# capstone_v1_1.net
KiCad netlist of a schematic drawn in Altium Designer
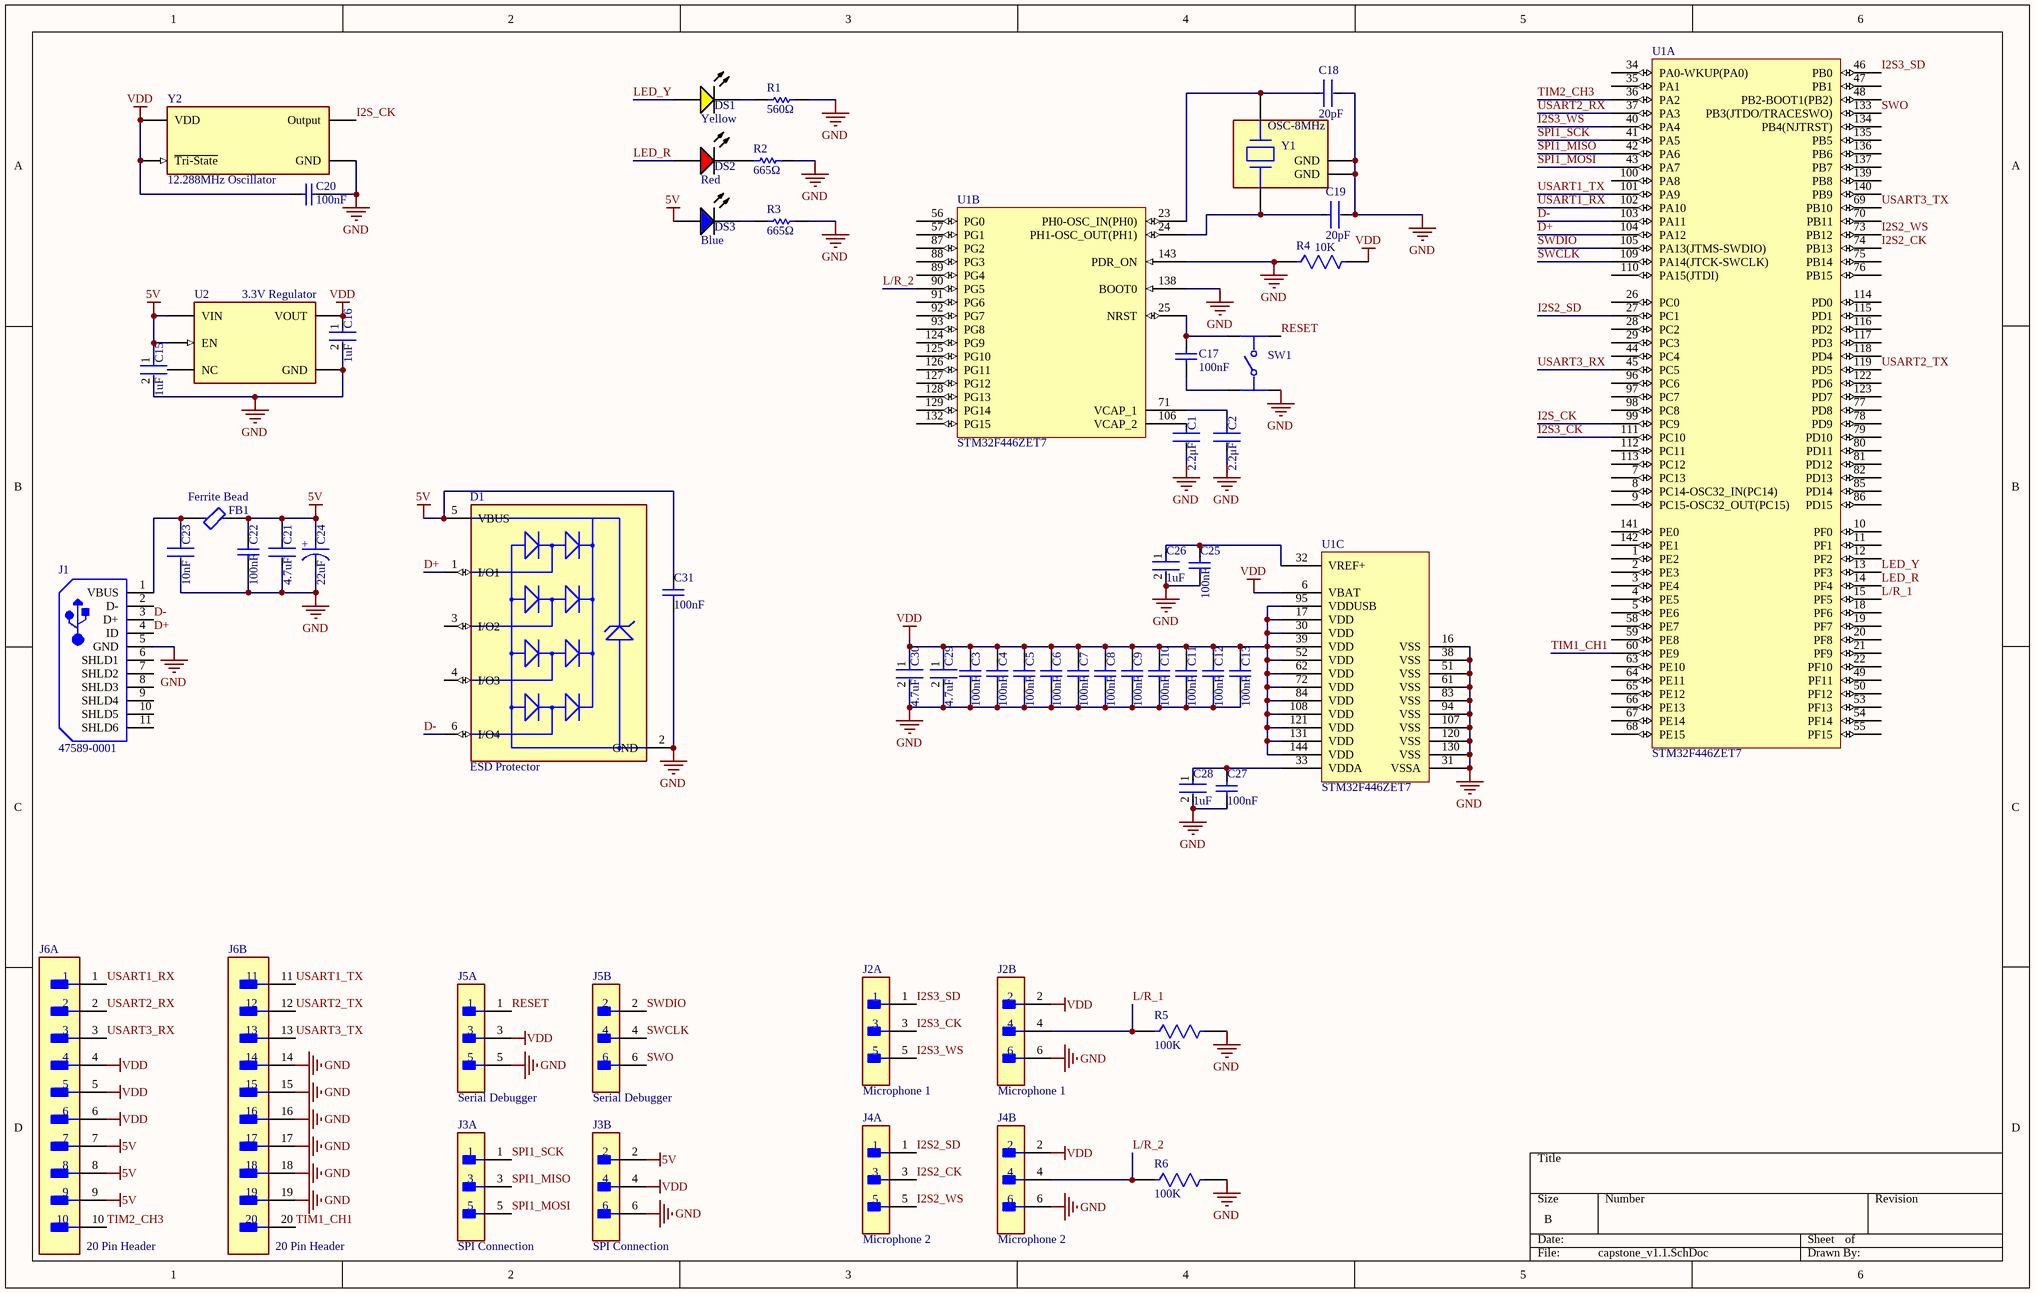
[diagram p0: capstone_v1.1.SchDoc]

(export (version "E")
  (design (tool "Eeschema 10.0.6"))
  (components
    (comp (ref "C1")
      (value "2.2μF")
      (footprint "FP-C1608-080-0_1-MFG")
      (description "Multilayer Ceramic Capacitors 2.2μF ±10% 35V X5R SMD 0603\r\nC1608X5R1V225K080AC")
      (fields (field (name "TOLERANCE") "10%") (field (name "VOLTAGE") "35V"))
      (libsource (lib "Altium Content Vault") (part "236180d848d6139a670b325ea6854c9"))
    )
    (comp (ref "C2")
      (value "2.2μF")
      (footprint "FP-C1608-080-0_1-MFG")
      (description "Multilayer Ceramic Capacitors 2.2μF ±10% 35V X5R SMD 0603\r\nC1608X5R1V225K080AC")
      (fields (field (name "TOLERANCE") "10%") (field (name "VOLTAGE") "35V"))
      (libsource (lib "Altium Content Vault") (part "236180d848d6139a670b325ea6854c9"))
    )
    (comp (ref "C3")
      (value "100nF")
      (footprint "SAMS-C0603-2_M")
      (fields (field (name "MANUFACTURER") "Samsung Electro-Mechanics"))
      (libsource (lib "Altium Content Vault") (part "CAP-NP-2"))
    )
    (comp (ref "C4")
      (value "100nF")
      (footprint "SAMS-C0603-2_M")
      (fields (field (name "MANUFACTURER") "Samsung Electro-Mechanics"))
      (libsource (lib "Altium Content Vault") (part "CAP-NP-2"))
    )
    (comp (ref "C5")
      (value "100nF")
      (footprint "SAMS-C0603-2_M")
      (fields (field (name "MANUFACTURER") "Samsung Electro-Mechanics"))
      (libsource (lib "Altium Content Vault") (part "CAP-NP-2"))
    )
    (comp (ref "C6")
      (value "100nF")
      (footprint "SAMS-C0603-2_M")
      (fields (field (name "MANUFACTURER") "Samsung Electro-Mechanics"))
      (libsource (lib "Altium Content Vault") (part "CAP-NP-2"))
    )
    (comp (ref "C7")
      (value "100nF")
      (footprint "SAMS-C0603-2_M")
      (fields (field (name "MANUFACTURER") "Samsung Electro-Mechanics"))
      (libsource (lib "Altium Content Vault") (part "CAP-NP-2"))
    )
    (comp (ref "C8")
      (value "100nF")
      (footprint "SAMS-C0603-2_M")
      (fields (field (name "MANUFACTURER") "Samsung Electro-Mechanics"))
      (libsource (lib "Altium Content Vault") (part "CAP-NP-2"))
    )
    (comp (ref "C9")
      (value "100nF")
      (footprint "SAMS-C0603-2_M")
      (fields (field (name "MANUFACTURER") "Samsung Electro-Mechanics"))
      (libsource (lib "Altium Content Vault") (part "CAP-NP-2"))
    )
    (comp (ref "C10")
      (value "100nF")
      (footprint "SAMS-C0603-2_M")
      (fields (field (name "MANUFACTURER") "Samsung Electro-Mechanics"))
      (libsource (lib "Altium Content Vault") (part "CAP-NP-2"))
    )
    (comp (ref "C11")
      (value "100nF")
      (footprint "SAMS-C0603-2_M")
      (fields (field (name "MANUFACTURER") "Samsung Electro-Mechanics"))
      (libsource (lib "Altium Content Vault") (part "CAP-NP-2"))
    )
    (comp (ref "C12")
      (value "100nF")
      (footprint "SAMS-C0603-2_M")
      (fields (field (name "MANUFACTURER") "Samsung Electro-Mechanics"))
      (libsource (lib "Altium Content Vault") (part "CAP-NP-2"))
    )
    (comp (ref "C13")
      (value "100nF")
      (footprint "SAMS-C0603-2_M")
      (fields (field (name "MANUFACTURER") "Samsung Electro-Mechanics"))
      (libsource (lib "Altium Content Vault") (part "CAP-NP-2"))
    )
    (comp (ref "C15")
      (value "1uF")
      (footprint "FP-0603-L_1_6_0_15-W_0_81-IPC_A")
      (description "General Purpose Ceramic Capacitor, 0603, 1uF, 10%, X5R, 15%, 10V\r\n0603ZD105KAT2A")
      (fields (field (name "TOLERANCE") "10%") (field (name "VOLTAGE") "10V"))
      (libsource (lib "Altium Content Vault") (part "02cd4be3c70576c341d710602a673aa"))
    )
    (comp (ref "C16")
      (value "1uF")
      (footprint "FP-0603-L_1_6_0_15-W_0_81-IPC_A")
      (description "General Purpose Ceramic Capacitor, 0603, 1uF, 10%, X5R, 15%, 10V\r\n0603ZD105KAT2A")
      (fields (field (name "TOLERANCE") "10%") (field (name "VOLTAGE") "10V"))
      (libsource (lib "Altium Content Vault") (part "02cd4be3c70576c341d710602a673aa"))
    )
    (comp (ref "C17")
      (value "100nF")
      (footprint "SAMS-C0603-2_M")
      (fields (field (name "MANUFACTURER") "Samsung Electro-Mechanics"))
      (libsource (lib "Altium Content Vault") (part "CAP-NP-2"))
    )
    (comp (ref "C18")
      (value "20pF")
      (footprint "FP-C0603C-CF-MFG")
      (description "CAP CER 20PF 50V 5% NP0 0603\r\nC0603C200J5GACTU")
      (fields
        (field (name "MANUFACTURER PART NUMBER") "C0603C200J5GACTU")
        (field (name "MANUFACTURER") "KEMET")
      )
      (libsource (lib "Altium Content Vault") (part "b4654b650e69147ec39a6b967a45e02"))
    )
    (comp (ref "C19")
      (value "20pF")
      (footprint "FP-C0603C-CF-MFG")
      (description "CAP CER 20PF 50V 5% NP0 0603\r\nC0603C200J5GACTU")
      (fields
        (field (name "MANUFACTURER PART NUMBER") "C0603C200J5GACTU")
        (field (name "MANUFACTURER") "KEMET")
      )
      (libsource (lib "Altium Content Vault") (part "b4654b650e69147ec39a6b967a45e02"))
    )
    (comp (ref "C20")
      (value "100nF")
      (footprint "SAMS-C0603-2_M")
      (fields (field (name "MANUFACTURER") "Samsung Electro-Mechanics"))
      (libsource (lib "Altium Content Vault") (part "CAP-NP-2"))
    )
    (comp (ref "C21")
      (value "4.7uF")
      (footprint "FP-C0603-CG-MFG")
      (description "CAP CER 4.7UF 6.3V X5R 0603\r\nC0603C475K9PACTU")
      (fields (field (name "TOLERANCE") "10%") (field (name "MANUFACTURER") "Kemet"))
      (libsource (lib "") (part "11868f565c42a9108669ba33697ecf6_1"))
    )
    (comp (ref "C22")
      (value "100nF")
      (footprint "SAMS-C0603-2_M")
      (fields (field (name "MANUFACTURER") "Samsung Electro-Mechanics"))
      (libsource (lib "Altium Content Vault") (part "CAP-NP-2"))
    )
    (comp (ref "C23")
      (value "10nF")
      (footprint "FP-0603-L_1_6_0_15-W_0_81-MFG")
      (description "General Purpose Ceramic Capacitor, 0603, 10nF, 10%, X7R, 15%, 50V")
      (fields (field (name "VOLTAGE") "50V") (field (name "TOLERANCE") "10%"))
      (libsource (lib "") (part "02cd4be3c70576c341d710602a673aa_1"))
    )
    (comp (ref "C24")
      (value "22uF")
      (footprint "FP-T491C226K010AT-MFG")
      (description "CAP TANT 22UF 10% 10V 2312\r\nT491C226K010AT")
      (fields (field (name "TOLERANCE") "20%") (field (name "VOLTAGE") "10V"))
      (libsource (lib "Altium Content Vault") (part "a00bbbee19879c290e62620ae7e47b1"))
    )
    (comp (ref "C25")
      (value "100nF")
      (footprint "SAMS-C0603-2_M")
      (fields (field (name "MANUFACTURER") "Samsung Electro-Mechanics"))
      (libsource (lib "Altium Content Vault") (part "CAP-NP-2"))
    )
    (comp (ref "C26")
      (value "1uF")
      (footprint "FP-0603-L_1_6_0_15-W_0_81-IPC_A")
      (description "General Purpose Ceramic Capacitor, 0603, 1uF, 10%, X5R, 15%, 10V\r\n0603ZD105KAT2A")
      (fields (field (name "TOLERANCE") "10%") (field (name "VOLTAGE") "10V"))
      (libsource (lib "Altium Content Vault") (part "02cd4be3c70576c341d710602a673aa"))
    )
    (comp (ref "C27")
      (value "100nF")
      (footprint "SAMS-C0603-2_M")
      (fields (field (name "MANUFACTURER") "Samsung Electro-Mechanics"))
      (libsource (lib "Altium Content Vault") (part "CAP-NP-2"))
    )
    (comp (ref "C28")
      (value "1uF")
      (footprint "FP-0603-L_1_6_0_15-W_0_81-IPC_A")
      (description "General Purpose Ceramic Capacitor, 0603, 1uF, 10%, X5R, 15%, 10V\r\n0603ZD105KAT2A")
      (fields (field (name "TOLERANCE") "10%") (field (name "VOLTAGE") "10V"))
      (libsource (lib "Altium Content Vault") (part "02cd4be3c70576c341d710602a673aa"))
    )
    (comp (ref "C29")
      (value "4.7uF")
      (footprint "FP-C0603-CG-MFG")
      (description "CAP CER 4.7UF 6.3V X5R 0603\r\nC0603C475K9PACTU")
      (fields (field (name "TOLERANCE") "10%") (field (name "MANUFACTURER") "Kemet"))
      (libsource (lib "Altium Content Vault") (part "11868f565c42a9108669ba33697ecf6"))
    )
    (comp (ref "C30")
      (value "4.7uF")
      (footprint "FP-C0603-CG-MFG")
      (description "CAP CER 4.7UF 6.3V X5R 0603\r\nC0603C475K9PACTU")
      (fields (field (name "TOLERANCE") "10%") (field (name "MANUFACTURER") "Kemet"))
      (libsource (lib "Altium Content Vault") (part "11868f565c42a9108669ba33697ecf6"))
    )
    (comp (ref "C31")
      (value "100nF")
      (footprint "SAMS-C0603-2_M")
      (fields (field (name "MANUFACTURER") "Samsung Electro-Mechanics"))
      (libsource (lib "Altium Content Vault") (part "CAP-NP-2"))
    )
    (comp (ref "D1")
      (value "ESD Protector")
      (footprint "FP-SOT23-6L-MFG")
      (description "TVS DIODE 5.25V 17V SOT23-6\r\nUSBLC6-4SC6")
      (fields
        (field (name "MANUFACTURER") "STMicroelectronics")
        (field (name "OCTOPART") "https://octopart.com/usblc6-4sc6-stmicroelectronics-347147")
      )
      (libsource (lib "Altium Content Vault") (part "3e70b616ccdc4c88b528e1820c4a7da"))
    )
    (comp (ref "DS1")
      (value "Yellow")
      (footprint "VISH-TLMY1000_V")
      (description "Low Current LED, 40 mW, -40 to 100 degC, 2-Pin SMD, RoHS, Tape and Reel\r\nTLMY1000-GS08")
      (fields (field (name "MANUFACTURER") "Vishay"))
      (libsource (lib "Altium Content Vault") (part "LED-YELLOW-AK-2"))
    )
    (comp (ref "DS2")
      (value "Red")
      (footprint "AVAG-HSMX-C190_V")
      (description "LED Uni-Color Red, 65 mW, 20 mA, -40 to 85 degC, 2-Pin SMD, RoHS, Tape and Reel\r\nHSMH-C190")
      (libsource (lib "Altium Content Vault") (part "LED-RED-AK-2"))
    )
    (comp (ref "DS3")
      (value "Blue")
      (footprint "AVAG-HSMX-C190_V")
      (description "LED Uni-Color Blue, 78 mW, 20 mA, -40 to 85 degC, 2-Pin SMD, RoHS, Tape and Reel\r\nHSMR-C190")
      (libsource (lib "Altium Content Vault") (part "LED-BLUE-AK-2"))
    )
    (comp (ref "FB1")
      (value "Ferrite Bead")
      (footprint "FP-BLM15-0_05-IPC_A")
      (description "Chip Ferrite Bead, 0402, 220Ω @ 100MHz, 0.1Ω, 25%, 1.4A\r\nBLM15PX221SN1D")
      (fields (field (name "TOLERANCE") "25%"))
      (libsource (lib "Altium Content Vault") (part "5f30dd21d616792df468990f7003faa"))
    )
    (comp (ref "J1")
      (value "47589-0001")
      (footprint "MOLX-47589-0001_V")
      (description "Right Angle Female Type AB Micro USB Connector, 30 V, 1.8 A, -30 to 85 degC, RoHS, Tape and Reel")
      (fields (field (name "MANUFACTURER") "Molex"))
      (libsource (lib "Altium Content Vault") (part "USB-5-6SHLD"))
    )
    (comp (ref "J2")
      (value "Microphone 1")
      (footprint "FP-M20-9980346-MFG")
      (description "CONN HEADER VERT 6POS 2.54MM\r\nM20-9980346")
      (fields (field (name "MANUFACTURER PART NUMBER") "M20-9980346") (field (name "MANUFACTURER") "Harwin"))
      (libsource (lib "Altium Content Vault") (part "2654a11fb13586ecb194516b1c997bc"))
    )
    (comp (ref "J3")
      (value "SPI Connection")
      (footprint "FP-M20-9980346-MFG")
      (description "CONN HEADER VERT 6POS 2.54MM\r\nM20-9980346")
      (fields (field (name "MANUFACTURER PART NUMBER") "M20-9980346") (field (name "MANUFACTURER") "Harwin"))
      (libsource (lib "Altium Content Vault") (part "2654a11fb13586ecb194516b1c997bc"))
    )
    (comp (ref "J4")
      (value "Microphone 2")
      (footprint "FP-M20-9980346-MFG")
      (description "CONN HEADER VERT 6POS 2.54MM\r\nM20-9980346")
      (fields (field (name "MANUFACTURER PART NUMBER") "M20-9980346") (field (name "MANUFACTURER") "Harwin"))
      (libsource (lib "Altium Content Vault") (part "2654a11fb13586ecb194516b1c997bc"))
    )
    (comp (ref "J5")
      (value "Serial Debugger")
      (footprint "FP-M20-9980346-MFG")
      (description "CONN HEADER VERT 6POS 2.54MM\r\nM20-9980346")
      (fields (field (name "MANUFACTURER PART NUMBER") "M20-9980346") (field (name "MANUFACTURER") "Harwin"))
      (libsource (lib "Altium Content Vault") (part "2654a11fb13586ecb194516b1c997bc"))
    )
    (comp (ref "J6")
      (value "20 Pin Header")
      (footprint "FP-TSW-110-08-G-D-MFG")
      (description "CONN HEADER VERT 20POS 2.54MM\r\nTSW-110-08-G-D")
      (fields
        (field (name "MANUFACTURER") "Samtec")
        (field (name "MANUFACTURER PART NUMBER") "TSW-110-08-G-D")
      )
      (libsource (lib "Altium Content Vault") (part "77e5b6e48cf913a9c6d5f7856d88bd2"))
    )
    (comp (ref "R1")
      (value "560Ω")
      (footprint "RESC1608X55X30ML15T15")
      (libsource (lib "Altium Content Vault") (part "RES-2"))
    )
    (comp (ref "R2")
      (value "665Ω")
      (footprint "RESC1608X55X30ML15T15")
      (description "ERJ-3EKF6650V")
      (fields (field (name "MANUFACTURER") "Panasonic"))
      (libsource (lib "Altium Content Vault") (part "RES"))
    )
    (comp (ref "R3")
      (value "665Ω")
      (footprint "RESC1608X55X30ML15T15")
      (description "ERJ-3EKF6650V")
      (fields (field (name "MANUFACTURER") "Panasonic"))
      (libsource (lib "Altium Content Vault") (part "RES"))
    )
    (comp (ref "R4")
      (value "10K")
      (footprint "FP-MCT0603-IPC_C")
      (description "RES SMD 100 OHM 1% 1/8W 0603\r\nMCT06030C1002FP500")
      (fields (field (name "TOLERANCE") "1%"))
      (libsource (lib "Altium Content Vault") (part "1029c3af85768c4190bb7ad29bc67b5"))
    )
    (comp (ref "R5")
      (value "100K")
      (footprint "FP-RC0603-0_55-MFG")
      (description "RES SMD 100K OHM 1% 1/10W 0603\r\nRC0603FR-07100KL")
      (fields (field (name "TOLERANCE") "1%"))
      (libsource (lib "Altium Content Vault") (part "1029c3af85768c4190bb7ad29bc67b5"))
    )
    (comp (ref "R6")
      (value "100K")
      (footprint "FP-RC0603-0_55-MFG")
      (description "RES SMD 100K OHM 1% 1/10W 0603\r\nRC0603FR-07100KL")
      (fields (field (name "TOLERANCE") "1%"))
      (libsource (lib "Altium Content Vault") (part "1029c3af85768c4190bb7ad29bc67b5"))
    )
    (comp (ref "SW1")
      (value "PTS645SM43SMTR92LFS")
      (footprint "FP-PTS645SM43SMTR92LFS-MFG")
      (description "SWITCH TACTILE SPST-NO 0.05A 12V")
      (libsource (lib "Altium Content Vault") (part "1adf0dd01260c80cf25a44bfd6b99ba"))
    )
    (comp (ref "U1")
      (value "STM32F446ZET7")
      (footprint "STM-LQFP144_M")
      (libsource (lib "Altium Content Vault") (part "MC-ARM-STM32F446-LQFP144"))
    )
    (comp (ref "U2")
      (value "3.3V Regulator")
      (footprint "FP-UJ-5-IPC_B")
      (description "IC REG LINEAR 3.3V 150MA TSOT5\r\nADP121-AUJZ33R7")
      (libsource (lib "Altium Content Vault") (part "0a093dae7315cdc977fd108dde87457"))
    )
    (comp (ref "Y1")
      (value "OSC-8MHz")
      (footprint "FP-ABM3B-MFG")
      (description "Crystal 8MHz ±20ppm 18pF SMD-4 5mm x 3.2mm\r\nABM3B-8.000MHZ-B2-T")
      (fields (field (name "TOLERANCE") "20ppm"))
      (libsource (lib "Altium Content Vault") (part "48e526d86b7f2615d98721063c72f49"))
    )
    (comp (ref "Y2")
      (value "12.288MHz Oscillator")
      (footprint "FP-ASFL1-MFG")
      (description "XTAL Oscillator 12.288MHz ±50ppm HCMOS, TTL 3.3V 4-SMD 5mm x 3.2mm\r\nASFL1-12.288MHZ-EC-T")
      (libsource (lib "Altium Content Vault") (part "47df00dc2349451232cb22fac08fbff"))
    )
  )
  (nets
    (net (code "1") (name "/D+") (class "Default")
      (node (ref "D1") (pin "1") (pinfunction "I/O1_1") (pintype "bidirectional"))
      (node (ref "J1") (pin "4") (pinfunction "ID_4") (pintype "passive"))
      (node (ref "U1") (pin "104") (pinfunction "PA12_104") (pintype "bidirectional"))
    )
    (net (code "2") (name "/D-") (class "Default")
      (node (ref "D1") (pin "6") (pinfunction "I/O4_6") (pintype "bidirectional"))
      (node (ref "J1") (pin "3") (pinfunction "D+_3") (pintype "passive"))
      (node (ref "U1") (pin "103") (pinfunction "PA11_103") (pintype "bidirectional"))
    )
    (net (code "3") (name "/I2S2_CK") (class "Default")
      (node (ref "J4") (pin "3") (pinfunction "3_3") (pintype "passive"))
      (node (ref "U1") (pin "74") (pinfunction "PB13_74") (pintype "bidirectional"))
    )
    (net (code "4") (name "/I2S2_SD") (class "Default")
      (node (ref "J4") (pin "1") (pinfunction "1_1") (pintype "passive"))
      (node (ref "U1") (pin "27") (pinfunction "PC1_27") (pintype "bidirectional"))
    )
    (net (code "5") (name "/I2S2_WS") (class "Default")
      (node (ref "J4") (pin "5") (pinfunction "5_5") (pintype "passive"))
      (node (ref "U1") (pin "73") (pinfunction "PB12_73") (pintype "bidirectional"))
    )
    (net (code "6") (name "/I2S3_CK") (class "Default")
      (node (ref "J2") (pin "3") (pinfunction "3_3") (pintype "passive"))
      (node (ref "U1") (pin "111") (pinfunction "PC10_111") (pintype "bidirectional"))
    )
    (net (code "7") (name "/I2S3_SD") (class "Default")
      (node (ref "J2") (pin "1") (pinfunction "1_1") (pintype "passive"))
      (node (ref "U1") (pin "46") (pinfunction "PB0_46") (pintype "bidirectional"))
    )
    (net (code "8") (name "/I2S3_WS") (class "Default")
      (node (ref "J2") (pin "5") (pinfunction "5_5") (pintype "passive"))
      (node (ref "U1") (pin "40") (pinfunction "PA4_40") (pintype "bidirectional"))
    )
    (net (code "9") (name "/I2S_CK") (class "Default")
      (node (ref "U1") (pin "99") (pinfunction "PC9_99") (pintype "bidirectional"))
      (node (ref "Y2") (pin "3") (pinfunction "Output_3") (pintype "passive"))
    )
    (net (code "10") (name "/LED_R") (class "Default")
      (node (ref "DS2") (pin "1") (pinfunction "A_1") (pintype "passive"))
      (node (ref "U1") (pin "14") (pinfunction "PF4_14") (pintype "bidirectional"))
    )
    (net (code "11") (name "/LED_Y") (class "Default")
      (node (ref "DS1") (pin "1") (pinfunction "A_1") (pintype "passive"))
      (node (ref "U1") (pin "13") (pinfunction "PF3_13") (pintype "bidirectional"))
    )
    (net (code "12") (name "/L{slash}R_1") (class "Default")
      (node (ref "J2") (pin "4") (pinfunction "4_4") (pintype "passive"))
      (node (ref "R5") (pin "1") (pinfunction "1_1") (pintype "passive"))
      (node (ref "U1") (pin "15") (pinfunction "PF5_15") (pintype "bidirectional"))
    )
    (net (code "13") (name "/L{slash}R_2") (class "Default")
      (node (ref "J4") (pin "4") (pinfunction "4_4") (pintype "passive"))
      (node (ref "R6") (pin "1") (pinfunction "1_1") (pintype "passive"))
      (node (ref "U1") (pin "90") (pinfunction "PG5_90") (pintype "bidirectional"))
    )
    (net (code "14") (name "/RESET") (class "Default")
      (node (ref "J5") (pin "1") (pinfunction "1_1") (pintype "passive"))
      (node (ref "SW1") (pin "2") (pinfunction "2_2") (pintype "passive"))
    )
    (net (code "15") (name "/SPI1_MISO") (class "Default")
      (node (ref "J3") (pin "3") (pinfunction "3_3") (pintype "passive"))
      (node (ref "U1") (pin "42") (pinfunction "PA6_42") (pintype "bidirectional"))
    )
    (net (code "16") (name "/SPI1_MOSI") (class "Default")
      (node (ref "J3") (pin "5") (pinfunction "5_5") (pintype "passive"))
      (node (ref "U1") (pin "43") (pinfunction "PA7_43") (pintype "bidirectional"))
    )
    (net (code "17") (name "/SPI1_SCK") (class "Default")
      (node (ref "J3") (pin "1") (pinfunction "1_1") (pintype "passive"))
      (node (ref "U1") (pin "41") (pinfunction "PA5_41") (pintype "bidirectional"))
    )
    (net (code "18") (name "/SWCLK") (class "Default")
      (node (ref "J5") (pin "4") (pinfunction "4_4") (pintype "passive"))
      (node (ref "U1") (pin "109") (pinfunction "PA14(JTCK-SWCLK)_109") (pintype "bidirectional"))
    )
    (net (code "19") (name "/SWDIO") (class "Default")
      (node (ref "J5") (pin "2") (pinfunction "2_2") (pintype "passive"))
      (node (ref "U1") (pin "105") (pinfunction "PA13(JTMS-SWDIO)_105") (pintype "bidirectional"))
    )
    (net (code "20") (name "/SWO") (class "Default")
      (node (ref "J5") (pin "6") (pinfunction "6_6") (pintype "passive"))
      (node (ref "U1") (pin "133") (pinfunction "PB3(JTDO/TRACESWO)_133") (pintype "bidirectional"))
    )
    (net (code "21") (name "/TIM1_CH1") (class "Default")
      (node (ref "J6") (pin "20") (pinfunction "20_20") (pintype "passive"))
      (node (ref "U1") (pin "60") (pinfunction "PE9_60") (pintype "bidirectional"))
    )
    (net (code "22") (name "/TIM2_CH3") (class "Default")
      (node (ref "J6") (pin "10") (pinfunction "10_10") (pintype "passive"))
      (node (ref "U1") (pin "36") (pinfunction "PA2_36") (pintype "bidirectional"))
    )
    (net (code "23") (name "/USART1_RX") (class "Default")
      (node (ref "J6") (pin "1") (pinfunction "1_1") (pintype "passive"))
      (node (ref "U1") (pin "102") (pinfunction "PA10_102") (pintype "bidirectional"))
    )
    (net (code "24") (name "/USART1_TX") (class "Default")
      (node (ref "J6") (pin "11") (pinfunction "11_11") (pintype "passive"))
      (node (ref "U1") (pin "101") (pinfunction "PA9_101") (pintype "bidirectional"))
    )
    (net (code "25") (name "/USART2_RX") (class "Default")
      (node (ref "J6") (pin "2") (pinfunction "2_2") (pintype "passive"))
      (node (ref "U1") (pin "37") (pinfunction "PA3_37") (pintype "bidirectional"))
    )
    (net (code "26") (name "/USART2_TX") (class "Default")
      (node (ref "J6") (pin "12") (pinfunction "12_12") (pintype "passive"))
      (node (ref "U1") (pin "119") (pinfunction "PD5_119") (pintype "bidirectional"))
    )
    (net (code "27") (name "/USART3_RX") (class "Default")
      (node (ref "J6") (pin "3") (pinfunction "3_3") (pintype "passive"))
      (node (ref "U1") (pin "45") (pinfunction "PC5_45") (pintype "bidirectional"))
    )
    (net (code "28") (name "/USART3_TX") (class "Default")
      (node (ref "J6") (pin "13") (pinfunction "13_13") (pintype "passive"))
      (node (ref "U1") (pin "69") (pinfunction "PB10_69") (pintype "bidirectional"))
    )
    (net (code "29") (name "5V") (class "Default")
      (node (ref "C15") (pin "1") (pinfunction "1_1") (pintype "passive"))
      (node (ref "C21") (pin "1") (pinfunction "1_1") (pintype "passive"))
      (node (ref "C22") (pin "2") (pinfunction "2_2") (pintype "passive"))
      (node (ref "C24") (pin "2") (pinfunction "A_2") (pintype "passive"))
      (node (ref "C31") (pin "2") (pinfunction "2_2") (pintype "passive"))
      (node (ref "D1") (pin "5") (pinfunction "VBUS_5") (pintype "power_in"))
      (node (ref "DS3") (pin "1") (pinfunction "A_1") (pintype "passive"))
      (node (ref "FB1") (pin "2") (pinfunction "2_2") (pintype "passive"))
      (node (ref "J3") (pin "2") (pinfunction "2_2") (pintype "passive"))
      (node (ref "J6") (pin "7") (pinfunction "7_7") (pintype "passive"))
      (node (ref "J6") (pin "8") (pinfunction "8_8") (pintype "passive"))
      (node (ref "J6") (pin "9") (pinfunction "9_9") (pintype "passive"))
      (node (ref "U2") (pin "1") (pinfunction "VIN_1") (pintype "power_in"))
      (node (ref "U2") (pin "3") (pinfunction "EN_3") (pintype "input"))
    )
    (net (code "30") (name "GND") (class "Default")
      (node (ref "C1") (pin "1") (pinfunction "1_1") (pintype "passive"))
      (node (ref "C10") (pin "1") (pinfunction "1_1") (pintype "passive"))
      (node (ref "C11") (pin "1") (pinfunction "1_1") (pintype "passive"))
      (node (ref "C12") (pin "1") (pinfunction "1_1") (pintype "passive"))
      (node (ref "C13") (pin "1") (pinfunction "1_1") (pintype "passive"))
      (node (ref "C15") (pin "2") (pinfunction "2_2") (pintype "passive"))
      (node (ref "C16") (pin "2") (pinfunction "2_2") (pintype "passive"))
      (node (ref "C18") (pin "2") (pinfunction "2_2") (pintype "passive"))
      (node (ref "C19") (pin "2") (pinfunction "2_2") (pintype "passive"))
      (node (ref "C2") (pin "1") (pinfunction "1_1") (pintype "passive"))
      (node (ref "C20") (pin "1") (pinfunction "1_1") (pintype "passive"))
      (node (ref "C21") (pin "2") (pinfunction "2_2") (pintype "passive"))
      (node (ref "C22") (pin "1") (pinfunction "1_1") (pintype "passive"))
      (node (ref "C23") (pin "2") (pinfunction "2_2") (pintype "passive"))
      (node (ref "C24") (pin "1") (pinfunction "C_1") (pintype "passive"))
      (node (ref "C25") (pin "1") (pinfunction "1_1") (pintype "passive"))
      (node (ref "C26") (pin "2") (pinfunction "2_2") (pintype "passive"))
      (node (ref "C27") (pin "1") (pinfunction "1_1") (pintype "passive"))
      (node (ref "C28") (pin "2") (pinfunction "2_2") (pintype "passive"))
      (node (ref "C29") (pin "2") (pinfunction "2_2") (pintype "passive"))
      (node (ref "C3") (pin "1") (pinfunction "1_1") (pintype "passive"))
      (node (ref "C30") (pin "2") (pinfunction "2_2") (pintype "passive"))
      (node (ref "C31") (pin "1") (pinfunction "1_1") (pintype "passive"))
      (node (ref "C4") (pin "1") (pinfunction "1_1") (pintype "passive"))
      (node (ref "C5") (pin "1") (pinfunction "1_1") (pintype "passive"))
      (node (ref "C6") (pin "1") (pinfunction "1_1") (pintype "passive"))
      (node (ref "C7") (pin "1") (pinfunction "1_1") (pintype "passive"))
      (node (ref "C8") (pin "1") (pinfunction "1_1") (pintype "passive"))
      (node (ref "C9") (pin "1") (pinfunction "1_1") (pintype "passive"))
      (node (ref "D1") (pin "2") (pinfunction "GND_2") (pintype "power_in"))
      (node (ref "J1") (pin "5") (pinfunction "GND_5") (pintype "passive"))
      (node (ref "J2") (pin "6") (pinfunction "6_6") (pintype "passive"))
      (node (ref "J3") (pin "6") (pinfunction "6_6") (pintype "passive"))
      (node (ref "J4") (pin "6") (pinfunction "6_6") (pintype "passive"))
      (node (ref "J5") (pin "5") (pinfunction "5_5") (pintype "passive"))
      (node (ref "J6") (pin "14") (pinfunction "14_14") (pintype "passive"))
      (node (ref "J6") (pin "15") (pinfunction "15_15") (pintype "passive"))
      (node (ref "J6") (pin "16") (pinfunction "16_16") (pintype "passive"))
      (node (ref "J6") (pin "17") (pinfunction "17_17") (pintype "passive"))
      (node (ref "J6") (pin "18") (pinfunction "18_18") (pintype "passive"))
      (node (ref "J6") (pin "19") (pinfunction "19_19") (pintype "passive"))
      (node (ref "R1") (pin "2") (pinfunction "2_2") (pintype "passive"))
      (node (ref "R2") (pin "2") (pinfunction "2_2") (pintype "passive"))
      (node (ref "R3") (pin "2") (pinfunction "2_2") (pintype "passive"))
      (node (ref "R4") (pin "1") (pinfunction "1_1") (pintype "passive"))
      (node (ref "R5") (pin "2") (pinfunction "2_2") (pintype "passive"))
      (node (ref "R6") (pin "2") (pinfunction "2_2") (pintype "passive"))
      (node (ref "SW1") (pin "4") (pinfunction "4_4") (pintype "passive"))
      (node (ref "U1") (pin "107") (pinfunction "VSS_107") (pintype "power_in"))
      (node (ref "U1") (pin "120") (pinfunction "VSS_120") (pintype "power_in"))
      (node (ref "U1") (pin "130") (pinfunction "VSS_130") (pintype "power_in"))
      (node (ref "U1") (pin "138") (pinfunction "BOOT0_138") (pintype "input"))
      (node (ref "U1") (pin "143") (pinfunction "PDR_ON_143") (pintype "input"))
      (node (ref "U1") (pin "16") (pinfunction "VSS_16") (pintype "power_in"))
      (node (ref "U1") (pin "31") (pinfunction "VSSA_31") (pintype "power_in"))
      (node (ref "U1") (pin "38") (pinfunction "VSS_38") (pintype "power_in"))
      (node (ref "U1") (pin "51") (pinfunction "VSS_51") (pintype "power_in"))
      (node (ref "U1") (pin "61") (pinfunction "VSS_61") (pintype "power_in"))
      (node (ref "U1") (pin "83") (pinfunction "VSS_83") (pintype "power_in"))
      (node (ref "U1") (pin "94") (pinfunction "VSS_94") (pintype "power_in"))
      (node (ref "U2") (pin "2") (pinfunction "GND_2") (pintype "power_in"))
      (node (ref "Y1") (pin "2") (pinfunction "GND_2") (pintype "power_in"))
      (node (ref "Y1") (pin "4") (pinfunction "GND_4") (pintype "power_in"))
      (node (ref "Y2") (pin "2") (pinfunction "GND_2") (pintype "power_in"))
    )
    (net (code "31") (name "Net-(C17-Pad1)") (class "Default")
      (node (ref "C17") (pin "1") (pinfunction "1_1") (pintype "passive"))
      (node (ref "SW1") (pin "3") (pinfunction "3_3") (pintype "passive"))
    )
    (net (code "32") (name "Net-(DS1-K)") (class "Default")
      (node (ref "DS1") (pin "2") (pinfunction "K_2") (pintype "passive"))
      (node (ref "R1") (pin "1") (pinfunction "1_1") (pintype "passive"))
    )
    (net (code "33") (name "Net-(DS2-K)") (class "Default")
      (node (ref "DS2") (pin "2") (pinfunction "K_2") (pintype "passive"))
      (node (ref "R2") (pin "1") (pinfunction "1_1") (pintype "passive"))
    )
    (net (code "34") (name "Net-(DS3-K)") (class "Default")
      (node (ref "DS3") (pin "2") (pinfunction "K_2") (pintype "passive"))
      (node (ref "R3") (pin "1") (pinfunction "1_1") (pintype "passive"))
    )
    (net (code "35") (name "Net-(J1-VBUS)") (class "Default")
      (node (ref "C23") (pin "1") (pinfunction "1_1") (pintype "passive"))
      (node (ref "FB1") (pin "1") (pinfunction "1_1") (pintype "passive"))
      (node (ref "J1") (pin "1") (pinfunction "VBUS_1") (pintype "passive"))
    )
    (net (code "36") (name "Net-(U1B-NRST)") (class "Default")
      (node (ref "C17") (pin "2") (pinfunction "2_2") (pintype "passive"))
      (node (ref "SW1") (pin "1") (pinfunction "1_1") (pintype "passive"))
      (node (ref "U1") (pin "25") (pinfunction "NRST_25") (pintype "bidirectional"))
    )
    (net (code "37") (name "Net-(U1B-PH0-OSC_IN(PH0))") (class "Default")
      (node (ref "C18") (pin "1") (pinfunction "1_1") (pintype "passive"))
      (node (ref "U1") (pin "23") (pinfunction "PH0-OSC_IN(PH0)_23") (pintype "bidirectional"))
      (node (ref "Y1") (pin "1") (pinfunction "1_1") (pintype "passive"))
    )
    (net (code "38") (name "Net-(U1B-PH1-OSC_OUT(PH1))") (class "Default")
      (node (ref "C19") (pin "1") (pinfunction "1_1") (pintype "passive"))
      (node (ref "U1") (pin "24") (pinfunction "PH1-OSC_OUT(PH1)_24") (pintype "bidirectional"))
      (node (ref "Y1") (pin "3") (pinfunction "3_3") (pintype "passive"))
    )
    (net (code "39") (name "Net-(U1B-VCAP_1)") (class "Default")
      (node (ref "C2") (pin "2") (pinfunction "2_2") (pintype "passive"))
      (node (ref "U1") (pin "71") (pinfunction "VCAP_1_71") (pintype "passive"))
    )
    (net (code "40") (name "Net-(U1B-VCAP_2)") (class "Default")
      (node (ref "C1") (pin "2") (pinfunction "2_2") (pintype "passive"))
      (node (ref "U1") (pin "106") (pinfunction "VCAP_2_106") (pintype "passive"))
    )
    (net (code "41") (name "Net-(U1C-VDDA)") (class "Default")
      (node (ref "C27") (pin "2") (pinfunction "2_2") (pintype "passive"))
      (node (ref "C28") (pin "1") (pinfunction "1_1") (pintype "passive"))
      (node (ref "U1") (pin "33") (pinfunction "VDDA_33") (pintype "power_in"))
    )
    (net (code "42") (name "Net-(U1C-VREF+)") (class "Default")
      (node (ref "C25") (pin "2") (pinfunction "2_2") (pintype "passive"))
      (node (ref "C26") (pin "1") (pinfunction "1_1") (pintype "passive"))
      (node (ref "U1") (pin "32") (pinfunction "VREF+_32") (pintype "power_in"))
    )
    (net (code "43") (name "VDD") (class "Default")
      (node (ref "C10") (pin "2") (pinfunction "2_2") (pintype "passive"))
      (node (ref "C11") (pin "2") (pinfunction "2_2") (pintype "passive"))
      (node (ref "C12") (pin "2") (pinfunction "2_2") (pintype "passive"))
      (node (ref "C13") (pin "2") (pinfunction "2_2") (pintype "passive"))
      (node (ref "C16") (pin "1") (pinfunction "1_1") (pintype "passive"))
      (node (ref "C20") (pin "2") (pinfunction "2_2") (pintype "passive"))
      (node (ref "C29") (pin "1") (pinfunction "1_1") (pintype "passive"))
      (node (ref "C3") (pin "2") (pinfunction "2_2") (pintype "passive"))
      (node (ref "C30") (pin "1") (pinfunction "1_1") (pintype "passive"))
      (node (ref "C4") (pin "2") (pinfunction "2_2") (pintype "passive"))
      (node (ref "C5") (pin "2") (pinfunction "2_2") (pintype "passive"))
      (node (ref "C6") (pin "2") (pinfunction "2_2") (pintype "passive"))
      (node (ref "C7") (pin "2") (pinfunction "2_2") (pintype "passive"))
      (node (ref "C8") (pin "2") (pinfunction "2_2") (pintype "passive"))
      (node (ref "C9") (pin "2") (pinfunction "2_2") (pintype "passive"))
      (node (ref "J2") (pin "2") (pinfunction "2_2") (pintype "passive"))
      (node (ref "J3") (pin "4") (pinfunction "4_4") (pintype "passive"))
      (node (ref "J4") (pin "2") (pinfunction "2_2") (pintype "passive"))
      (node (ref "J5") (pin "3") (pinfunction "3_3") (pintype "passive"))
      (node (ref "J6") (pin "4") (pinfunction "4_4") (pintype "passive"))
      (node (ref "J6") (pin "5") (pinfunction "5_5") (pintype "passive"))
      (node (ref "J6") (pin "6") (pinfunction "6_6") (pintype "passive"))
      (node (ref "R4") (pin "2") (pinfunction "2_2") (pintype "passive"))
      (node (ref "U1") (pin "108") (pinfunction "VDD_108") (pintype "power_in"))
      (node (ref "U1") (pin "121") (pinfunction "VDD_121") (pintype "power_in"))
      (node (ref "U1") (pin "131") (pinfunction "VDD_131") (pintype "power_in"))
      (node (ref "U1") (pin "144") (pinfunction "VDD_144") (pintype "power_in"))
      (node (ref "U1") (pin "17") (pinfunction "VDD_17") (pintype "power_in"))
      (node (ref "U1") (pin "30") (pinfunction "VDD_30") (pintype "power_in"))
      (node (ref "U1") (pin "39") (pinfunction "VDD_39") (pintype "power_in"))
      (node (ref "U1") (pin "52") (pinfunction "VDD_52") (pintype "power_in"))
      (node (ref "U1") (pin "6") (pinfunction "VBAT_6") (pintype "power_in"))
      (node (ref "U1") (pin "62") (pinfunction "VDD_62") (pintype "power_in"))
      (node (ref "U1") (pin "72") (pinfunction "VDD_72") (pintype "power_in"))
      (node (ref "U1") (pin "84") (pinfunction "VDD_84") (pintype "power_in"))
      (node (ref "U1") (pin "95") (pinfunction "VDDUSB_95") (pintype "power_in"))
      (node (ref "U2") (pin "5") (pinfunction "VOUT_5") (pintype "power_in"))
      (node (ref "Y2") (pin "1") (pinfunction "~{Tri-State}_1") (pintype "input"))
      (node (ref "Y2") (pin "4") (pinfunction "VDD_4") (pintype "power_in"))
    )
    (net (code "44") (name "unconnected-(D1-I{slash}O2-Pad3)") (class "Default")
      (node (ref "D1") (pin "3") (pinfunction "I/O2_3") (pintype "bidirectional"))
    )
    (net (code "45") (name "unconnected-(D1-I{slash}O3-Pad4)") (class "Default")
      (node (ref "D1") (pin "4") (pinfunction "I/O3_4") (pintype "bidirectional"))
    )
    (net (code "46") (name "unconnected-(J1-D--Pad2)") (class "Default")
      (node (ref "J1") (pin "2") (pinfunction "D-_2") (pintype "passive"))
    )
    (net (code "47") (name "unconnected-(J1-SHLD1-Pad6)") (class "Default")
      (node (ref "J1") (pin "6") (pinfunction "SHLD1_6") (pintype "passive"))
    )
    (net (code "48") (name "unconnected-(J1-SHLD2-Pad7)") (class "Default")
      (node (ref "J1") (pin "7") (pinfunction "SHLD2_7") (pintype "passive"))
    )
    (net (code "49") (name "unconnected-(J1-SHLD3-Pad8)") (class "Default")
      (node (ref "J1") (pin "8") (pinfunction "SHLD3_8") (pintype "passive"))
    )
    (net (code "50") (name "unconnected-(J1-SHLD4-Pad9)") (class "Default")
      (node (ref "J1") (pin "9") (pinfunction "SHLD4_9") (pintype "passive"))
    )
    (net (code "51") (name "unconnected-(J1-SHLD5-Pad10)") (class "Default")
      (node (ref "J1") (pin "10") (pinfunction "SHLD5_10") (pintype "passive"))
    )
    (net (code "52") (name "unconnected-(J1-SHLD6-Pad11)") (class "Default")
      (node (ref "J1") (pin "11") (pinfunction "SHLD6_11") (pintype "passive"))
    )
    (net (code "53") (name "unconnected-(U1A-PA0-WKUP(PA0)-Pad34)") (class "Default")
      (node (ref "U1") (pin "34") (pinfunction "PA0-WKUP(PA0)_34") (pintype "bidirectional"))
    )
    (net (code "54") (name "unconnected-(U1A-PA1-Pad35)") (class "Default")
      (node (ref "U1") (pin "35") (pinfunction "PA1_35") (pintype "bidirectional"))
    )
    (net (code "55") (name "unconnected-(U1A-PA8-Pad100)") (class "Default")
      (node (ref "U1") (pin "100") (pinfunction "PA8_100") (pintype "bidirectional"))
    )
    (net (code "56") (name "unconnected-(U1A-PA15(JTDI)-Pad110)") (class "Default")
      (node (ref "U1") (pin "110") (pinfunction "PA15(JTDI)_110") (pintype "bidirectional"))
    )
    (net (code "57") (name "unconnected-(U1A-PB1-Pad47)") (class "Default")
      (node (ref "U1") (pin "47") (pinfunction "PB1_47") (pintype "bidirectional"))
    )
    (net (code "58") (name "unconnected-(U1A-PB2-BOOT1(PB2)-Pad48)") (class "Default")
      (node (ref "U1") (pin "48") (pinfunction "PB2-BOOT1(PB2)_48") (pintype "bidirectional"))
    )
    (net (code "59") (name "unconnected-(U1A-PB4(NJTRST)-Pad134)") (class "Default")
      (node (ref "U1") (pin "134") (pinfunction "PB4(NJTRST)_134") (pintype "bidirectional"))
    )
    (net (code "60") (name "unconnected-(U1A-PB5-Pad135)") (class "Default")
      (node (ref "U1") (pin "135") (pinfunction "PB5_135") (pintype "bidirectional"))
    )
    (net (code "61") (name "unconnected-(U1A-PB6-Pad136)") (class "Default")
      (node (ref "U1") (pin "136") (pinfunction "PB6_136") (pintype "bidirectional"))
    )
    (net (code "62") (name "unconnected-(U1A-PB7-Pad137)") (class "Default")
      (node (ref "U1") (pin "137") (pinfunction "PB7_137") (pintype "bidirectional"))
    )
    (net (code "63") (name "unconnected-(U1A-PB8-Pad139)") (class "Default")
      (node (ref "U1") (pin "139") (pinfunction "PB8_139") (pintype "bidirectional"))
    )
    (net (code "64") (name "unconnected-(U1A-PB9-Pad140)") (class "Default")
      (node (ref "U1") (pin "140") (pinfunction "PB9_140") (pintype "bidirectional"))
    )
    (net (code "65") (name "unconnected-(U1A-PB11-Pad70)") (class "Default")
      (node (ref "U1") (pin "70") (pinfunction "PB11_70") (pintype "bidirectional"))
    )
    (net (code "66") (name "unconnected-(U1A-PB14-Pad75)") (class "Default")
      (node (ref "U1") (pin "75") (pinfunction "PB14_75") (pintype "bidirectional"))
    )
    (net (code "67") (name "unconnected-(U1A-PB15-Pad76)") (class "Default")
      (node (ref "U1") (pin "76") (pinfunction "PB15_76") (pintype "bidirectional"))
    )
    (net (code "68") (name "unconnected-(U1A-PC0-Pad26)") (class "Default")
      (node (ref "U1") (pin "26") (pinfunction "PC0_26") (pintype "bidirectional"))
    )
    (net (code "69") (name "unconnected-(U1A-PC2-Pad28)") (class "Default")
      (node (ref "U1") (pin "28") (pinfunction "PC2_28") (pintype "bidirectional"))
    )
    (net (code "70") (name "unconnected-(U1A-PC3-Pad29)") (class "Default")
      (node (ref "U1") (pin "29") (pinfunction "PC3_29") (pintype "bidirectional"))
    )
    (net (code "71") (name "unconnected-(U1A-PC4-Pad44)") (class "Default")
      (node (ref "U1") (pin "44") (pinfunction "PC4_44") (pintype "bidirectional"))
    )
    (net (code "72") (name "unconnected-(U1A-PC6-Pad96)") (class "Default")
      (node (ref "U1") (pin "96") (pinfunction "PC6_96") (pintype "bidirectional"))
    )
    (net (code "73") (name "unconnected-(U1A-PC7-Pad97)") (class "Default")
      (node (ref "U1") (pin "97") (pinfunction "PC7_97") (pintype "bidirectional"))
    )
    (net (code "74") (name "unconnected-(U1A-PC8-Pad98)") (class "Default")
      (node (ref "U1") (pin "98") (pinfunction "PC8_98") (pintype "bidirectional"))
    )
    (net (code "75") (name "unconnected-(U1A-PC11-Pad112)") (class "Default")
      (node (ref "U1") (pin "112") (pinfunction "PC11_112") (pintype "bidirectional"))
    )
    (net (code "76") (name "unconnected-(U1A-PC12-Pad113)") (class "Default")
      (node (ref "U1") (pin "113") (pinfunction "PC12_113") (pintype "bidirectional"))
    )
    (net (code "77") (name "unconnected-(U1A-PC13-Pad7)") (class "Default")
      (node (ref "U1") (pin "7") (pinfunction "PC13_7") (pintype "bidirectional"))
    )
    (net (code "78") (name "unconnected-(U1A-PC14-OSC32_IN(PC14)-Pad8)") (class "Default")
      (node (ref "U1") (pin "8") (pinfunction "PC14-OSC32_IN(PC14)_8") (pintype "bidirectional"))
    )
    (net (code "79") (name "unconnected-(U1A-PC15-OSC32_OUT(PC15)-Pad9)") (class "Default")
      (node (ref "U1") (pin "9") (pinfunction "PC15-OSC32_OUT(PC15)_9") (pintype "bidirectional"))
    )
    (net (code "80") (name "unconnected-(U1A-PD0-Pad114)") (class "Default")
      (node (ref "U1") (pin "114") (pinfunction "PD0_114") (pintype "bidirectional"))
    )
    (net (code "81") (name "unconnected-(U1A-PD1-Pad115)") (class "Default")
      (node (ref "U1") (pin "115") (pinfunction "PD1_115") (pintype "bidirectional"))
    )
    (net (code "82") (name "unconnected-(U1A-PD2-Pad116)") (class "Default")
      (node (ref "U1") (pin "116") (pinfunction "PD2_116") (pintype "bidirectional"))
    )
    (net (code "83") (name "unconnected-(U1A-PD3-Pad117)") (class "Default")
      (node (ref "U1") (pin "117") (pinfunction "PD3_117") (pintype "bidirectional"))
    )
    (net (code "84") (name "unconnected-(U1A-PD4-Pad118)") (class "Default")
      (node (ref "U1") (pin "118") (pinfunction "PD4_118") (pintype "bidirectional"))
    )
    (net (code "85") (name "unconnected-(U1A-PD6-Pad122)") (class "Default")
      (node (ref "U1") (pin "122") (pinfunction "PD6_122") (pintype "bidirectional"))
    )
    (net (code "86") (name "unconnected-(U1A-PD7-Pad123)") (class "Default")
      (node (ref "U1") (pin "123") (pinfunction "PD7_123") (pintype "bidirectional"))
    )
    (net (code "87") (name "unconnected-(U1A-PD8-Pad77)") (class "Default")
      (node (ref "U1") (pin "77") (pinfunction "PD8_77") (pintype "bidirectional"))
    )
    (net (code "88") (name "unconnected-(U1A-PD9-Pad78)") (class "Default")
      (node (ref "U1") (pin "78") (pinfunction "PD9_78") (pintype "bidirectional"))
    )
    (net (code "89") (name "unconnected-(U1A-PD10-Pad79)") (class "Default")
      (node (ref "U1") (pin "79") (pinfunction "PD10_79") (pintype "bidirectional"))
    )
    (net (code "90") (name "unconnected-(U1A-PD11-Pad80)") (class "Default")
      (node (ref "U1") (pin "80") (pinfunction "PD11_80") (pintype "bidirectional"))
    )
    (net (code "91") (name "unconnected-(U1A-PD12-Pad81)") (class "Default")
      (node (ref "U1") (pin "81") (pinfunction "PD12_81") (pintype "bidirectional"))
    )
    (net (code "92") (name "unconnected-(U1A-PD13-Pad82)") (class "Default")
      (node (ref "U1") (pin "82") (pinfunction "PD13_82") (pintype "bidirectional"))
    )
    (net (code "93") (name "unconnected-(U1A-PD14-Pad85)") (class "Default")
      (node (ref "U1") (pin "85") (pinfunction "PD14_85") (pintype "bidirectional"))
    )
    (net (code "94") (name "unconnected-(U1A-PD15-Pad86)") (class "Default")
      (node (ref "U1") (pin "86") (pinfunction "PD15_86") (pintype "bidirectional"))
    )
    (net (code "95") (name "unconnected-(U1A-PE0-Pad141)") (class "Default")
      (node (ref "U1") (pin "141") (pinfunction "PE0_141") (pintype "bidirectional"))
    )
    (net (code "96") (name "unconnected-(U1A-PE1-Pad142)") (class "Default")
      (node (ref "U1") (pin "142") (pinfunction "PE1_142") (pintype "bidirectional"))
    )
    (net (code "97") (name "unconnected-(U1A-PE2-Pad1)") (class "Default")
      (node (ref "U1") (pin "1") (pinfunction "PE2_1") (pintype "bidirectional"))
    )
    (net (code "98") (name "unconnected-(U1A-PE3-Pad2)") (class "Default")
      (node (ref "U1") (pin "2") (pinfunction "PE3_2") (pintype "bidirectional"))
    )
    (net (code "99") (name "unconnected-(U1A-PE4-Pad3)") (class "Default")
      (node (ref "U1") (pin "3") (pinfunction "PE4_3") (pintype "bidirectional"))
    )
    (net (code "100") (name "unconnected-(U1A-PE5-Pad4)") (class "Default")
      (node (ref "U1") (pin "4") (pinfunction "PE5_4") (pintype "bidirectional"))
    )
    (net (code "101") (name "unconnected-(U1A-PE6-Pad5)") (class "Default")
      (node (ref "U1") (pin "5") (pinfunction "PE6_5") (pintype "bidirectional"))
    )
    (net (code "102") (name "unconnected-(U1A-PE7-Pad58)") (class "Default")
      (node (ref "U1") (pin "58") (pinfunction "PE7_58") (pintype "bidirectional"))
    )
    (net (code "103") (name "unconnected-(U1A-PE8-Pad59)") (class "Default")
      (node (ref "U1") (pin "59") (pinfunction "PE8_59") (pintype "bidirectional"))
    )
    (net (code "104") (name "unconnected-(U1A-PE10-Pad63)") (class "Default")
      (node (ref "U1") (pin "63") (pinfunction "PE10_63") (pintype "bidirectional"))
    )
    (net (code "105") (name "unconnected-(U1A-PE11-Pad64)") (class "Default")
      (node (ref "U1") (pin "64") (pinfunction "PE11_64") (pintype "bidirectional"))
    )
    (net (code "106") (name "unconnected-(U1A-PE12-Pad65)") (class "Default")
      (node (ref "U1") (pin "65") (pinfunction "PE12_65") (pintype "bidirectional"))
    )
    (net (code "107") (name "unconnected-(U1A-PE13-Pad66)") (class "Default")
      (node (ref "U1") (pin "66") (pinfunction "PE13_66") (pintype "bidirectional"))
    )
    (net (code "108") (name "unconnected-(U1A-PE14-Pad67)") (class "Default")
      (node (ref "U1") (pin "67") (pinfunction "PE14_67") (pintype "bidirectional"))
    )
    (net (code "109") (name "unconnected-(U1A-PE15-Pad68)") (class "Default")
      (node (ref "U1") (pin "68") (pinfunction "PE15_68") (pintype "bidirectional"))
    )
    (net (code "110") (name "unconnected-(U1A-PF0-Pad10)") (class "Default")
      (node (ref "U1") (pin "10") (pinfunction "PF0_10") (pintype "bidirectional"))
    )
    (net (code "111") (name "unconnected-(U1A-PF1-Pad11)") (class "Default")
      (node (ref "U1") (pin "11") (pinfunction "PF1_11") (pintype "bidirectional"))
    )
    (net (code "112") (name "unconnected-(U1A-PF2-Pad12)") (class "Default")
      (node (ref "U1") (pin "12") (pinfunction "PF2_12") (pintype "bidirectional"))
    )
    (net (code "113") (name "unconnected-(U1A-PF6-Pad18)") (class "Default")
      (node (ref "U1") (pin "18") (pinfunction "PF6_18") (pintype "bidirectional"))
    )
    (net (code "114") (name "unconnected-(U1A-PF7-Pad19)") (class "Default")
      (node (ref "U1") (pin "19") (pinfunction "PF7_19") (pintype "bidirectional"))
    )
    (net (code "115") (name "unconnected-(U1A-PF8-Pad20)") (class "Default")
      (node (ref "U1") (pin "20") (pinfunction "PF8_20") (pintype "bidirectional"))
    )
    (net (code "116") (name "unconnected-(U1A-PF9-Pad21)") (class "Default")
      (node (ref "U1") (pin "21") (pinfunction "PF9_21") (pintype "bidirectional"))
    )
    (net (code "117") (name "unconnected-(U1A-PF10-Pad22)") (class "Default")
      (node (ref "U1") (pin "22") (pinfunction "PF10_22") (pintype "bidirectional"))
    )
    (net (code "118") (name "unconnected-(U1A-PF11-Pad49)") (class "Default")
      (node (ref "U1") (pin "49") (pinfunction "PF11_49") (pintype "bidirectional"))
    )
    (net (code "119") (name "unconnected-(U1A-PF12-Pad50)") (class "Default")
      (node (ref "U1") (pin "50") (pinfunction "PF12_50") (pintype "bidirectional"))
    )
    (net (code "120") (name "unconnected-(U1A-PF13-Pad53)") (class "Default")
      (node (ref "U1") (pin "53") (pinfunction "PF13_53") (pintype "bidirectional"))
    )
    (net (code "121") (name "unconnected-(U1A-PF14-Pad54)") (class "Default")
      (node (ref "U1") (pin "54") (pinfunction "PF14_54") (pintype "bidirectional"))
    )
    (net (code "122") (name "unconnected-(U1A-PF15-Pad55)") (class "Default")
      (node (ref "U1") (pin "55") (pinfunction "PF15_55") (pintype "bidirectional"))
    )
    (net (code "123") (name "unconnected-(U1B-PG0-Pad56)") (class "Default")
      (node (ref "U1") (pin "56") (pinfunction "PG0_56") (pintype "bidirectional"))
    )
    (net (code "124") (name "unconnected-(U1B-PG1-Pad57)") (class "Default")
      (node (ref "U1") (pin "57") (pinfunction "PG1_57") (pintype "bidirectional"))
    )
    (net (code "125") (name "unconnected-(U1B-PG2-Pad87)") (class "Default")
      (node (ref "U1") (pin "87") (pinfunction "PG2_87") (pintype "bidirectional"))
    )
    (net (code "126") (name "unconnected-(U1B-PG3-Pad88)") (class "Default")
      (node (ref "U1") (pin "88") (pinfunction "PG3_88") (pintype "bidirectional"))
    )
    (net (code "127") (name "unconnected-(U1B-PG4-Pad89)") (class "Default")
      (node (ref "U1") (pin "89") (pinfunction "PG4_89") (pintype "bidirectional"))
    )
    (net (code "128") (name "unconnected-(U1B-PG6-Pad91)") (class "Default")
      (node (ref "U1") (pin "91") (pinfunction "PG6_91") (pintype "bidirectional"))
    )
    (net (code "129") (name "unconnected-(U1B-PG7-Pad92)") (class "Default")
      (node (ref "U1") (pin "92") (pinfunction "PG7_92") (pintype "bidirectional"))
    )
    (net (code "130") (name "unconnected-(U1B-PG8-Pad93)") (class "Default")
      (node (ref "U1") (pin "93") (pinfunction "PG8_93") (pintype "bidirectional"))
    )
    (net (code "131") (name "unconnected-(U1B-PG9-Pad124)") (class "Default")
      (node (ref "U1") (pin "124") (pinfunction "PG9_124") (pintype "bidirectional"))
    )
    (net (code "132") (name "unconnected-(U1B-PG10-Pad125)") (class "Default")
      (node (ref "U1") (pin "125") (pinfunction "PG10_125") (pintype "bidirectional"))
    )
    (net (code "133") (name "unconnected-(U1B-PG11-Pad126)") (class "Default")
      (node (ref "U1") (pin "126") (pinfunction "PG11_126") (pintype "bidirectional"))
    )
    (net (code "134") (name "unconnected-(U1B-PG12-Pad127)") (class "Default")
      (node (ref "U1") (pin "127") (pinfunction "PG12_127") (pintype "bidirectional"))
    )
    (net (code "135") (name "unconnected-(U1B-PG13-Pad128)") (class "Default")
      (node (ref "U1") (pin "128") (pinfunction "PG13_128") (pintype "bidirectional"))
    )
    (net (code "136") (name "unconnected-(U1B-PG14-Pad129)") (class "Default")
      (node (ref "U1") (pin "129") (pinfunction "PG14_129") (pintype "bidirectional"))
    )
    (net (code "137") (name "unconnected-(U1B-PG15-Pad132)") (class "Default")
      (node (ref "U1") (pin "132") (pinfunction "PG15_132") (pintype "bidirectional"))
    )
    (net (code "138") (name "unconnected-(U2-NC-Pad4)") (class "Default")
      (node (ref "U2") (pin "4") (pinfunction "NC_4") (pintype "passive"))
    )
  )
)
